# chalupa.net
KiCad netlist of a schematic drawn in EAGLE
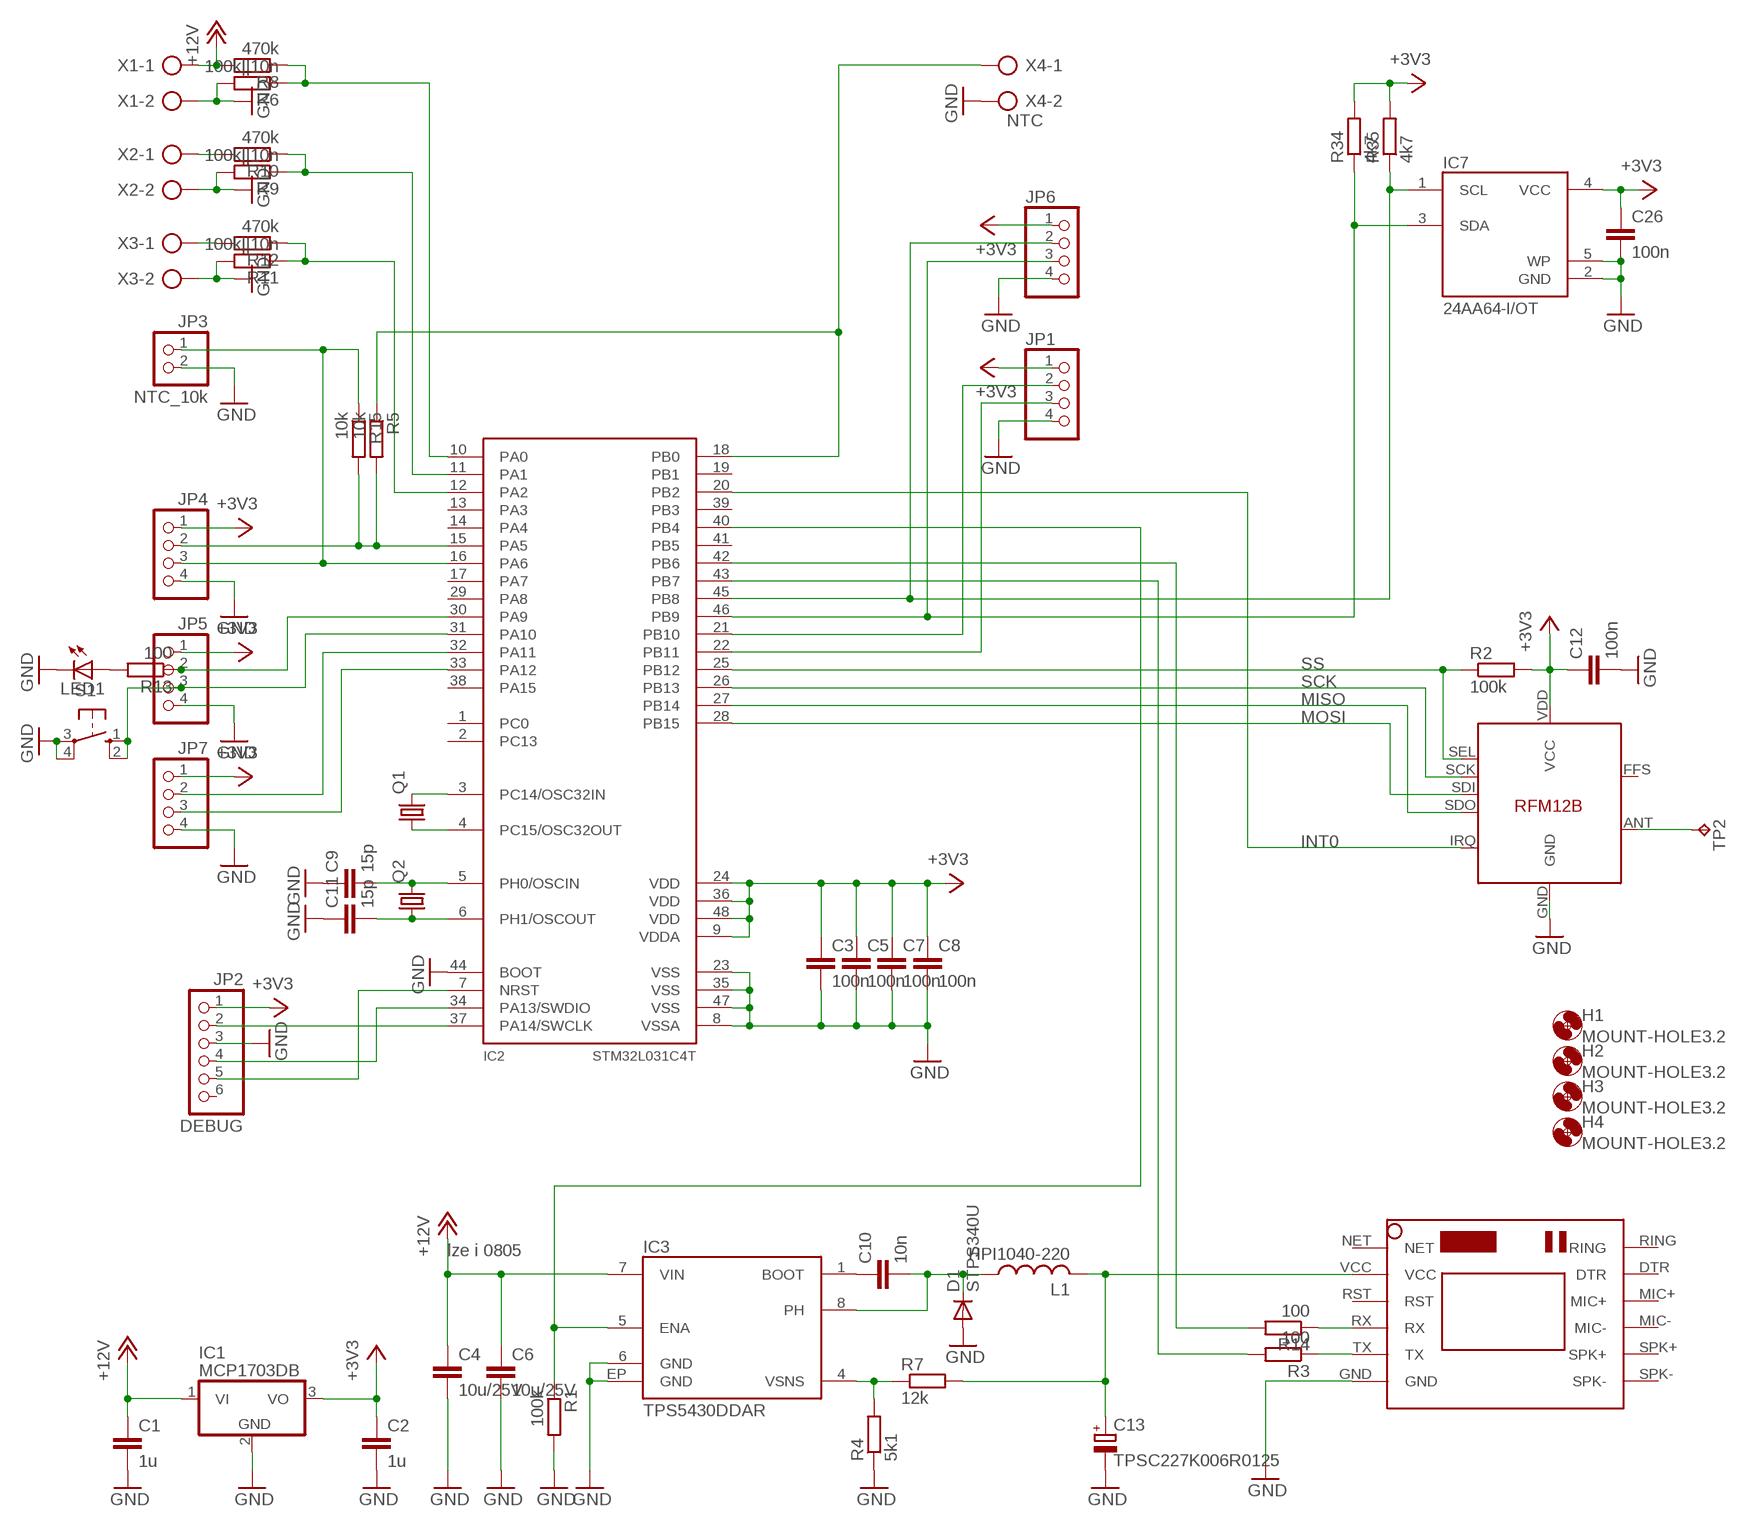
[diagram p0: schematic, sheet 1]

(export (version "E")
  (design (tool "Eeschema 10.0.6"))
  (components
    (comp (ref "C1")
      (value "1u")
      (footprint "eagle-import:C0603")
      (libsource (lib "eagle-import") (part "C-EUC0603"))
    )
    (comp (ref "C2")
      (value "1u")
      (footprint "eagle-import:C0603")
      (libsource (lib "eagle-import") (part "C-EUC0603"))
    )
    (comp (ref "C3")
      (value "100n")
      (footprint "eagle-import:C0603")
      (libsource (lib "eagle-import") (part "C-EUC0603"))
    )
    (comp (ref "C4")
      (value "10u/25V")
      (footprint "eagle-import:C1206")
      (libsource (lib "eagle-import") (part "C-EUC1206"))
    )
    (comp (ref "C5")
      (value "100n")
      (footprint "eagle-import:C0603")
      (libsource (lib "eagle-import") (part "C-EUC0603"))
    )
    (comp (ref "C6")
      (value "10u/25V")
      (footprint "eagle-import:C1206")
      (libsource (lib "eagle-import") (part "C-EUC1206"))
    )
    (comp (ref "C7")
      (value "100n")
      (footprint "eagle-import:C0603")
      (libsource (lib "eagle-import") (part "C-EUC0603"))
    )
    (comp (ref "C8")
      (value "100n")
      (footprint "eagle-import:C0603")
      (libsource (lib "eagle-import") (part "C-EUC0603"))
    )
    (comp (ref "C9")
      (value "15p")
      (footprint "eagle-import:C0603")
      (libsource (lib "eagle-import") (part "C-EUC0603"))
    )
    (comp (ref "C10")
      (value "10n")
      (footprint "eagle-import:C0603")
      (libsource (lib "eagle-import") (part "C-EUC0603"))
    )
    (comp (ref "C11")
      (value "15p")
      (footprint "eagle-import:C0603")
      (libsource (lib "eagle-import") (part "C-EUC0603"))
    )
    (comp (ref "C12")
      (value "100n")
      (footprint "eagle-import:C0603")
      (libsource (lib "eagle-import") (part "C-EUC0603"))
    )
    (comp (ref "C13")
      (value "TPSC227K006R0125")
      (footprint "eagle-import:SMC_C")
      (libsource (lib "eagle-import") (part "CPOL-EUSMCC"))
    )
    (comp (ref "C26")
      (value "100n")
      (footprint "eagle-import:C0603")
      (libsource (lib "eagle-import") (part "C-EUC0603"))
    )
    (comp (ref "D1")
      (value "STPS340U")
      (footprint "eagle-import:SMB")
      (libsource (lib "eagle-import") (part "DIODE-SMB"))
    )
    (comp (ref "H1")
      (value "MOUNT-HOLE3.2")
      (footprint "eagle-import:3,2")
      (libsource (lib "eagle-import") (part "MOUNT-HOLE3.2"))
    )
    (comp (ref "H2")
      (value "MOUNT-HOLE3.2")
      (footprint "eagle-import:3,2")
      (libsource (lib "eagle-import") (part "MOUNT-HOLE3.2"))
    )
    (comp (ref "H3")
      (value "MOUNT-HOLE3.2")
      (footprint "eagle-import:3,2")
      (libsource (lib "eagle-import") (part "MOUNT-HOLE3.2"))
    )
    (comp (ref "H4")
      (value "MOUNT-HOLE3.2")
      (footprint "eagle-import:3,2")
      (libsource (lib "eagle-import") (part "MOUNT-HOLE3.2"))
    )
    (comp (ref "IC1")
      (value "MCP1703DB")
      (footprint "eagle-import:SOT223")
      (libsource (lib "eagle-import") (part "MCP1703DB"))
    )
    (comp (ref "IC2")
      (value "STM32L031C4T")
      (footprint "eagle-import:LQFP48")
      (libsource (lib "eagle-import") (part "STM32L031C4T"))
    )
    (comp (ref "IC3")
      (value "TPS5430DDAR")
      (footprint "eagle-import:DDA")
      (libsource (lib "eagle-import") (part "TPS5430DDA"))
    )
    (comp (ref "IC5")
      (value "SIM800LMODULE")
      (footprint "eagle-import:SIM800LMODULE")
      (libsource (lib "eagle-import") (part "SIM800LMODULE"))
    )
    (comp (ref "IC7")
      (value "24AA64-I/OT")
      (footprint "eagle-import:SOT23-5")
      (libsource (lib "eagle-import") (part "24AA64-I/OT"))
    )
    (comp (ref "JP1")
      (value "PINHD-1X4")
      (footprint "eagle-import:1X04")
      (libsource (lib "eagle-import") (part "PINHD-1X4"))
    )
    (comp (ref "JP2")
      (value "DEBUG")
      (footprint "eagle-import:1X06")
      (libsource (lib "eagle-import") (part "PINHD-1X6"))
    )
    (comp (ref "JP3")
      (value "NTC_10k")
      (footprint "eagle-import:1X02")
      (libsource (lib "eagle-import") (part "PINHD-1X2"))
    )
    (comp (ref "JP4")
      (value "PINHD-1X4")
      (footprint "eagle-import:1X04")
      (libsource (lib "eagle-import") (part "PINHD-1X4"))
    )
    (comp (ref "JP5")
      (value "PINHD-1X4")
      (footprint "eagle-import:1X04")
      (libsource (lib "eagle-import") (part "PINHD-1X4"))
    )
    (comp (ref "JP6")
      (value "PINHD-1X4")
      (footprint "eagle-import:1X04")
      (libsource (lib "eagle-import") (part "PINHD-1X4"))
    )
    (comp (ref "JP7")
      (value "PINHD-1X4")
      (footprint "eagle-import:1X04")
      (libsource (lib "eagle-import") (part "PINHD-1X4"))
    )
    (comp (ref "L1")
      (value "HPI1040-220")
      (footprint "eagle-import:HPI1040")
      (libsource (lib "eagle-import") (part "L-USHPI1040"))
    )
    (comp (ref "LED1")
      (value "LEDCHIP-LED0805")
      (footprint "eagle-import:CHIP-LED0805")
      (libsource (lib "eagle-import") (part "LEDCHIP-LED0805"))
    )
    (comp (ref "Q1")
      (value "CRYSTALTC38H")
      (footprint "eagle-import:TC38H")
      (libsource (lib "eagle-import") (part "CRYSTALTC38H"))
    )
    (comp (ref "Q2")
      (value "CRYSTALHC49UP")
      (footprint "eagle-import:HC49UP")
      (libsource (lib "eagle-import") (part "CRYSTALHC49UP"))
    )
    (comp (ref "R1")
      (value "100k")
      (footprint "eagle-import:R0603")
      (libsource (lib "eagle-import") (part "R-EU_R0603"))
    )
    (comp (ref "R2")
      (value "100k")
      (footprint "eagle-import:R0603")
      (libsource (lib "eagle-import") (part "R-EU_R0603"))
    )
    (comp (ref "R3")
      (value "100")
      (footprint "eagle-import:R0603")
      (libsource (lib "eagle-import") (part "R-EU_R0603"))
    )
    (comp (ref "R4")
      (value "5k1")
      (footprint "eagle-import:R0603")
      (libsource (lib "eagle-import") (part "R-EU_R0603"))
    )
    (comp (ref "R5")
      (value "10k")
      (footprint "eagle-import:R0603")
      (libsource (lib "eagle-import") (part "R-EU_R0603"))
    )
    (comp (ref "R6")
      (value "100k||10n")
      (footprint "eagle-import:R0603")
      (libsource (lib "eagle-import") (part "R-EU_R0603"))
    )
    (comp (ref "R7")
      (value "12k")
      (footprint "eagle-import:R0603")
      (libsource (lib "eagle-import") (part "R-EU_R0603"))
    )
    (comp (ref "R8")
      (value "470k")
      (footprint "eagle-import:R0603")
      (libsource (lib "eagle-import") (part "R-EU_R0603"))
    )
    (comp (ref "R9")
      (value "100k||10n")
      (footprint "eagle-import:R0603")
      (libsource (lib "eagle-import") (part "R-EU_R0603"))
    )
    (comp (ref "R10")
      (value "470k")
      (footprint "eagle-import:R0603")
      (libsource (lib "eagle-import") (part "R-EU_R0603"))
    )
    (comp (ref "R11")
      (value "100k||10n")
      (footprint "eagle-import:R0603")
      (libsource (lib "eagle-import") (part "R-EU_R0603"))
    )
    (comp (ref "R12")
      (value "470k")
      (footprint "eagle-import:R0603")
      (libsource (lib "eagle-import") (part "R-EU_R0603"))
    )
    (comp (ref "R13")
      (value "100")
      (footprint "eagle-import:R0603")
      (libsource (lib "eagle-import") (part "R-EU_R0603"))
    )
    (comp (ref "R14")
      (value "100")
      (footprint "eagle-import:R0603")
      (libsource (lib "eagle-import") (part "R-EU_R0603"))
    )
    (comp (ref "R15")
      (value "10k")
      (footprint "eagle-import:R0603")
      (libsource (lib "eagle-import") (part "R-EU_R0603"))
    )
    (comp (ref "R34")
      (value "4k7")
      (footprint "eagle-import:R0603")
      (libsource (lib "eagle-import") (part "R-EU_R0603"))
    )
    (comp (ref "R35")
      (value "4k7")
      (footprint "eagle-import:R0603")
      (libsource (lib "eagle-import") (part "R-EU_R0603"))
    )
    (comp (ref "RFM12B")
      (value "RFM12B")
      (footprint "eagle-import:RFM12B")
      (libsource (lib "eagle-import") (part "RFM12B"))
    )
    (comp (ref "S1")
      (value "10-XX")
      (footprint "eagle-import:B3F-10XX")
      (fields (field (name "MPN") "B3F-1000"))
      (libsource (lib "eagle-import") (part "10-XX"))
    )
    (comp (ref "TP2")
      (value "TPB2,54")
      (footprint "eagle-import:B2,54")
      (libsource (lib "eagle-import") (part "TPB2,54"))
    )
    (comp (ref "X1")
      (value "AK500/2")
      (footprint "eagle-import:AK500_2")
      (libsource (lib "eagle-import") (part "AK500/2"))
    )
    (comp (ref "X2")
      (value "AK500/2")
      (footprint "eagle-import:AK500_2")
      (libsource (lib "eagle-import") (part "AK500/2"))
    )
    (comp (ref "X3")
      (value "AK500/2")
      (footprint "eagle-import:AK500_2")
      (libsource (lib "eagle-import") (part "AK500/2"))
    )
    (comp (ref "X4")
      (value "NTC")
      (footprint "eagle-import:AK500_2")
      (libsource (lib "eagle-import") (part "AK500/2"))
    )
  )
  (nets
    (net (code "1") (name "+3V3") (class "Default")
      (node (ref "C12") (pin "1") (pinfunction "1_1") (pintype "passive"))
      (node (ref "C2") (pin "1") (pinfunction "1_1") (pintype "passive"))
      (node (ref "C26") (pin "1") (pinfunction "1_1") (pintype "passive"))
      (node (ref "C3") (pin "1") (pinfunction "1_1") (pintype "passive"))
      (node (ref "C5") (pin "1") (pinfunction "1_1") (pintype "passive"))
      (node (ref "C7") (pin "1") (pinfunction "1_1") (pintype "passive"))
      (node (ref "C8") (pin "1") (pinfunction "1_1") (pintype "passive"))
      (node (ref "IC1") (pin "3") (pinfunction "VO_3") (pintype "passive"))
      (node (ref "IC2") (pin "24") (pinfunction "VDD_24") (pintype "power_in"))
      (node (ref "IC2") (pin "36") (pinfunction "VDD_36") (pintype "power_in"))
      (node (ref "IC2") (pin "48") (pinfunction "VDD_48") (pintype "power_in"))
      (node (ref "IC2") (pin "9") (pinfunction "VDDA_9") (pintype "power_in"))
      (node (ref "IC7") (pin "4") (pinfunction "VCC_4") (pintype "power_in"))
      (node (ref "JP1") (pin "1") (pinfunction "1_1") (pintype "passive"))
      (node (ref "JP2") (pin "1") (pinfunction "1_1") (pintype "passive"))
      (node (ref "JP4") (pin "1") (pinfunction "1_1") (pintype "passive"))
      (node (ref "JP5") (pin "1") (pinfunction "1_1") (pintype "passive"))
      (node (ref "JP6") (pin "1") (pinfunction "1_1") (pintype "passive"))
      (node (ref "JP7") (pin "1") (pinfunction "1_1") (pintype "passive"))
      (node (ref "R2") (pin "2") (pinfunction "2_2") (pintype "passive"))
      (node (ref "R34") (pin "2") (pinfunction "2_2") (pintype "passive"))
      (node (ref "R35") (pin "2") (pinfunction "2_2") (pintype "passive"))
      (node (ref "RFM12B") (pin "VDD") (pinfunction "VCC_VDD") (pintype "power_in"))
    )
    (net (code "2") (name "+12V") (class "Default")
      (node (ref "C1") (pin "1") (pinfunction "1_1") (pintype "passive"))
      (node (ref "C4") (pin "1") (pinfunction "1_1") (pintype "passive"))
      (node (ref "C6") (pin "1") (pinfunction "1_1") (pintype "passive"))
      (node (ref "IC1") (pin "1") (pinfunction "VI_1") (pintype "input"))
      (node (ref "IC3") (pin "7") (pinfunction "VIN_7") (pintype "power_in"))
      (node (ref "R8") (pin "2") (pinfunction "2_2") (pintype "passive"))
      (node (ref "X1") (pin "1") (pinfunction "KL_1") (pintype "passive"))
    )
    (net (code "3") (name "/INT0") (class "Default")
      (node (ref "IC2") (pin "20") (pinfunction "PB2_20") (pintype "bidirectional"))
      (node (ref "RFM12B") (pin "IRQ") (pinfunction "IRQ_IRQ") (pintype "open_collector"))
    )
    (net (code "4") (name "/MISO") (class "Default")
      (node (ref "IC2") (pin "27") (pinfunction "PB14_27") (pintype "bidirectional"))
      (node (ref "RFM12B") (pin "SDO") (pinfunction "SDO_SDO") (pintype "output"))
    )
    (net (code "5") (name "/MOSI") (class "Default")
      (node (ref "IC2") (pin "28") (pinfunction "PB15_28") (pintype "bidirectional"))
      (node (ref "RFM12B") (pin "SDI") (pinfunction "SDI_SDI") (pintype "input"))
    )
    (net (code "6") (name "/SCK") (class "Default")
      (node (ref "IC2") (pin "26") (pinfunction "PB13_26") (pintype "bidirectional"))
      (node (ref "RFM12B") (pin "SCK") (pinfunction "SCK_SCK") (pintype "input"))
    )
    (net (code "7") (name "/SS") (class "Default")
      (node (ref "IC2") (pin "25") (pinfunction "PB12_25") (pintype "bidirectional"))
      (node (ref "R2") (pin "1") (pinfunction "1_1") (pintype "passive"))
      (node (ref "RFM12B") (pin "SEL") (pinfunction "SEL_SEL") (pintype "input"))
    )
    (net (code "8") (name "GND") (class "Default")
      (node (ref "C1") (pin "2") (pinfunction "2_2") (pintype "passive"))
      (node (ref "C11") (pin "1") (pinfunction "1_1") (pintype "passive"))
      (node (ref "C12") (pin "2") (pinfunction "2_2") (pintype "passive"))
      (node (ref "C13") (pin "-") (pinfunction "-_-") (pintype "passive"))
      (node (ref "C2") (pin "2") (pinfunction "2_2") (pintype "passive"))
      (node (ref "C26") (pin "2") (pinfunction "2_2") (pintype "passive"))
      (node (ref "C3") (pin "2") (pinfunction "2_2") (pintype "passive"))
      (node (ref "C4") (pin "2") (pinfunction "2_2") (pintype "passive"))
      (node (ref "C5") (pin "2") (pinfunction "2_2") (pintype "passive"))
      (node (ref "C6") (pin "2") (pinfunction "2_2") (pintype "passive"))
      (node (ref "C7") (pin "2") (pinfunction "2_2") (pintype "passive"))
      (node (ref "C8") (pin "2") (pinfunction "2_2") (pintype "passive"))
      (node (ref "C9") (pin "1") (pinfunction "1_1") (pintype "passive"))
      (node (ref "D1") (pin "A") (pinfunction "A_A") (pintype "passive"))
      (node (ref "IC1") (pin "2") (pinfunction "GND_2") (pintype "passive"))
      (node (ref "IC2") (pin "23") (pinfunction "VSS_23") (pintype "power_in"))
      (node (ref "IC2") (pin "35") (pinfunction "VSS_35") (pintype "power_in"))
      (node (ref "IC2") (pin "44") (pinfunction "BOOT_44") (pintype "bidirectional"))
      (node (ref "IC2") (pin "47") (pinfunction "VSS_47") (pintype "power_in"))
      (node (ref "IC2") (pin "8") (pinfunction "VSSA_8") (pintype "power_in"))
      (node (ref "IC3") (pin "6") (pinfunction "GND_6") (pintype "power_in"))
      (node (ref "IC3") (pin "EP") (pinfunction "GND_EP") (pintype "power_in"))
      (node (ref "IC5") (pin "GND") (pinfunction "GND_GND") (pintype "bidirectional"))
      (node (ref "IC7") (pin "2") (pinfunction "GND_2") (pintype "power_in"))
      (node (ref "IC7") (pin "5") (pinfunction "WP_5") (pintype "input"))
      (node (ref "JP1") (pin "4") (pinfunction "4_4") (pintype "passive"))
      (node (ref "JP2") (pin "3") (pinfunction "3_3") (pintype "passive"))
      (node (ref "JP3") (pin "2") (pinfunction "2_2") (pintype "passive"))
      (node (ref "JP4") (pin "4") (pinfunction "4_4") (pintype "passive"))
      (node (ref "JP5") (pin "4") (pinfunction "4_4") (pintype "passive"))
      (node (ref "JP6") (pin "4") (pinfunction "4_4") (pintype "passive"))
      (node (ref "JP7") (pin "4") (pinfunction "4_4") (pintype "passive"))
      (node (ref "LED1") (pin "C") (pinfunction "C_C") (pintype "passive"))
      (node (ref "R1") (pin "2") (pinfunction "2_2") (pintype "passive"))
      (node (ref "R11") (pin "2") (pinfunction "2_2") (pintype "passive"))
      (node (ref "R4") (pin "1") (pinfunction "1_1") (pintype "passive"))
      (node (ref "R6") (pin "2") (pinfunction "2_2") (pintype "passive"))
      (node (ref "R9") (pin "2") (pinfunction "2_2") (pintype "passive"))
      (node (ref "RFM12B") (pin "GND") (pinfunction "GND_GND") (pintype "power_in"))
      (node (ref "S1") (pin "3") (pinfunction "P_3") (pintype "passive"))
      (node (ref "S1") (pin "4") (pinfunction "P1_4") (pintype "passive"))
      (node (ref "X1") (pin "2") (pinfunction "KL_2") (pintype "passive"))
      (node (ref "X2") (pin "2") (pinfunction "KL_2") (pintype "passive"))
      (node (ref "X3") (pin "2") (pinfunction "KL_2") (pintype "passive"))
      (node (ref "X4") (pin "2") (pinfunction "KL_2") (pintype "passive"))
    )
    (net (code "9") (name "Net-(C13-Pad+)") (class "Default")
      (node (ref "C13") (pin "+") (pinfunction "+_+") (pintype "passive"))
      (node (ref "IC5") (pin "VCC") (pinfunction "VCC_VCC") (pintype "bidirectional"))
      (node (ref "L1") (pin "2") (pinfunction "2_2") (pintype "passive"))
      (node (ref "R7") (pin "2") (pinfunction "2_2") (pintype "passive"))
    )
    (net (code "10") (name "Net-(IC2-NRST)") (class "Default")
      (node (ref "IC2") (pin "7") (pinfunction "NRST_7") (pintype "bidirectional"))
      (node (ref "JP2") (pin "5") (pinfunction "5_5") (pintype "passive"))
    )
    (net (code "11") (name "Net-(IC2-PA0)") (class "Default")
      (node (ref "IC2") (pin "10") (pinfunction "PA0_10") (pintype "bidirectional"))
      (node (ref "R6") (pin "1") (pinfunction "1_1") (pintype "passive"))
      (node (ref "R8") (pin "1") (pinfunction "1_1") (pintype "passive"))
    )
    (net (code "12") (name "Net-(IC2-PA1)") (class "Default")
      (node (ref "IC2") (pin "11") (pinfunction "PA1_11") (pintype "bidirectional"))
      (node (ref "R10") (pin "1") (pinfunction "1_1") (pintype "passive"))
      (node (ref "R9") (pin "1") (pinfunction "1_1") (pintype "passive"))
    )
    (net (code "13") (name "Net-(IC2-PA2)") (class "Default")
      (node (ref "IC2") (pin "12") (pinfunction "PA2_12") (pintype "bidirectional"))
      (node (ref "R11") (pin "1") (pinfunction "1_1") (pintype "passive"))
      (node (ref "R12") (pin "1") (pinfunction "1_1") (pintype "passive"))
    )
    (net (code "14") (name "Net-(IC2-PA5)") (class "Default")
      (node (ref "IC2") (pin "15") (pinfunction "PA5_15") (pintype "bidirectional"))
      (node (ref "JP4") (pin "2") (pinfunction "2_2") (pintype "passive"))
      (node (ref "R15") (pin "2") (pinfunction "2_2") (pintype "passive"))
      (node (ref "R5") (pin "2") (pinfunction "2_2") (pintype "passive"))
    )
    (net (code "15") (name "Net-(IC2-PA6)") (class "Default")
      (node (ref "IC2") (pin "16") (pinfunction "PA6_16") (pintype "bidirectional"))
      (node (ref "JP3") (pin "1") (pinfunction "1_1") (pintype "passive"))
      (node (ref "JP4") (pin "3") (pinfunction "3_3") (pintype "passive"))
      (node (ref "R15") (pin "1") (pinfunction "1_1") (pintype "passive"))
    )
    (net (code "16") (name "Net-(IC2-PA9)") (class "Default")
      (node (ref "IC2") (pin "30") (pinfunction "PA9_30") (pintype "bidirectional"))
      (node (ref "JP5") (pin "2") (pinfunction "2_2") (pintype "passive"))
      (node (ref "R13") (pin "1") (pinfunction "1_1") (pintype "passive"))
    )
    (net (code "17") (name "Net-(IC2-PA10)") (class "Default")
      (node (ref "IC2") (pin "31") (pinfunction "PA10_31") (pintype "bidirectional"))
      (node (ref "JP5") (pin "3") (pinfunction "3_3") (pintype "passive"))
      (node (ref "S1") (pin "1") (pinfunction "S_1") (pintype "passive"))
      (node (ref "S1") (pin "2") (pinfunction "S1_2") (pintype "passive"))
    )
    (net (code "18") (name "Net-(IC2-PA11)") (class "Default")
      (node (ref "IC2") (pin "32") (pinfunction "PA11_32") (pintype "bidirectional"))
      (node (ref "JP7") (pin "2") (pinfunction "2_2") (pintype "passive"))
    )
    (net (code "19") (name "Net-(IC2-PA12)") (class "Default")
      (node (ref "IC2") (pin "33") (pinfunction "PA12_33") (pintype "bidirectional"))
      (node (ref "JP7") (pin "3") (pinfunction "3_3") (pintype "passive"))
    )
    (net (code "20") (name "Net-(IC2-PA13{slash}SWDIO)") (class "Default")
      (node (ref "IC2") (pin "34") (pinfunction "PA13/SWDIO_34") (pintype "bidirectional"))
      (node (ref "JP2") (pin "4") (pinfunction "4_4") (pintype "passive"))
    )
    (net (code "21") (name "Net-(IC2-PA14{slash}SWCLK)") (class "Default")
      (node (ref "IC2") (pin "37") (pinfunction "PA14/SWCLK_37") (pintype "bidirectional"))
      (node (ref "JP2") (pin "2") (pinfunction "2_2") (pintype "passive"))
    )
    (net (code "22") (name "Net-(IC2-PB0)") (class "Default")
      (node (ref "IC2") (pin "18") (pinfunction "PB0_18") (pintype "bidirectional"))
      (node (ref "R5") (pin "1") (pinfunction "1_1") (pintype "passive"))
      (node (ref "X4") (pin "1") (pinfunction "KL_1") (pintype "passive"))
    )
    (net (code "23") (name "Net-(IC2-PB4)") (class "Default")
      (node (ref "IC2") (pin "40") (pinfunction "PB4_40") (pintype "bidirectional"))
      (node (ref "IC3") (pin "5") (pinfunction "ENA_5") (pintype "bidirectional"))
      (node (ref "R1") (pin "1") (pinfunction "1_1") (pintype "passive"))
    )
    (net (code "24") (name "Net-(IC2-PB6)") (class "Default")
      (node (ref "IC2") (pin "42") (pinfunction "PB6_42") (pintype "bidirectional"))
      (node (ref "R14") (pin "2") (pinfunction "2_2") (pintype "passive"))
    )
    (net (code "25") (name "Net-(IC2-PB7)") (class "Default")
      (node (ref "IC2") (pin "43") (pinfunction "PB7_43") (pintype "bidirectional"))
      (node (ref "R3") (pin "2") (pinfunction "2_2") (pintype "passive"))
    )
    (net (code "26") (name "Net-(IC2-PB8)") (class "Default")
      (node (ref "IC2") (pin "45") (pinfunction "PB8_45") (pintype "bidirectional"))
      (node (ref "IC7") (pin "1") (pinfunction "SCL_1") (pintype "input"))
      (node (ref "JP6") (pin "2") (pinfunction "2_2") (pintype "passive"))
      (node (ref "R35") (pin "1") (pinfunction "1_1") (pintype "passive"))
    )
    (net (code "27") (name "Net-(IC2-PB9)") (class "Default")
      (node (ref "IC2") (pin "46") (pinfunction "PB9_46") (pintype "bidirectional"))
      (node (ref "IC7") (pin "3") (pinfunction "SDA_3") (pintype "bidirectional"))
      (node (ref "JP6") (pin "3") (pinfunction "3_3") (pintype "passive"))
      (node (ref "R34") (pin "1") (pinfunction "1_1") (pintype "passive"))
    )
    (net (code "28") (name "Net-(IC2-PB10)") (class "Default")
      (node (ref "IC2") (pin "21") (pinfunction "PB10_21") (pintype "bidirectional"))
      (node (ref "JP1") (pin "2") (pinfunction "2_2") (pintype "passive"))
    )
    (net (code "29") (name "Net-(IC2-PB11)") (class "Default")
      (node (ref "IC2") (pin "22") (pinfunction "PB11_22") (pintype "bidirectional"))
      (node (ref "JP1") (pin "3") (pinfunction "3_3") (pintype "passive"))
    )
    (net (code "30") (name "Net-(IC2-PC14{slash}OSC32IN)") (class "Default")
      (node (ref "IC2") (pin "3") (pinfunction "PC14/OSC32IN_3") (pintype "passive"))
      (node (ref "Q1") (pin "2") (pinfunction "2_2") (pintype "passive"))
    )
    (net (code "31") (name "Net-(IC2-PC15{slash}OSC32OUT)") (class "Default")
      (node (ref "IC2") (pin "4") (pinfunction "PC15/OSC32OUT_4") (pintype "passive"))
      (node (ref "Q1") (pin "1") (pinfunction "1_1") (pintype "passive"))
    )
    (net (code "32") (name "Net-(IC2-PH0{slash}OSCIN)") (class "Default")
      (node (ref "C9") (pin "2") (pinfunction "2_2") (pintype "passive"))
      (node (ref "IC2") (pin "5") (pinfunction "PH0/OSCIN_5") (pintype "passive"))
      (node (ref "Q2") (pin "2") (pinfunction "2_2") (pintype "passive"))
    )
    (net (code "33") (name "Net-(IC2-PH1{slash}OSCOUT)") (class "Default")
      (node (ref "C11") (pin "2") (pinfunction "2_2") (pintype "passive"))
      (node (ref "IC2") (pin "6") (pinfunction "PH1/OSCOUT_6") (pintype "passive"))
      (node (ref "Q2") (pin "1") (pinfunction "1_1") (pintype "passive"))
    )
    (net (code "34") (name "Net-(IC3-BOOT)") (class "Default")
      (node (ref "C10") (pin "1") (pinfunction "1_1") (pintype "passive"))
      (node (ref "IC3") (pin "1") (pinfunction "BOOT_1") (pintype "passive"))
    )
    (net (code "35") (name "Net-(IC3-PH)") (class "Default")
      (node (ref "C10") (pin "2") (pinfunction "2_2") (pintype "passive"))
      (node (ref "D1") (pin "C") (pinfunction "C_C") (pintype "passive"))
      (node (ref "IC3") (pin "8") (pinfunction "PH_8") (pintype "passive"))
      (node (ref "L1") (pin "1") (pinfunction "1_1") (pintype "passive"))
    )
    (net (code "36") (name "Net-(IC3-VSNS)") (class "Default")
      (node (ref "IC3") (pin "4") (pinfunction "VSNS_4") (pintype "input"))
      (node (ref "R4") (pin "2") (pinfunction "2_2") (pintype "passive"))
      (node (ref "R7") (pin "1") (pinfunction "1_1") (pintype "passive"))
    )
    (net (code "37") (name "Net-(IC5-PadRX)") (class "Default")
      (node (ref "IC5") (pin "RX") (pinfunction "RX_RX") (pintype "bidirectional"))
      (node (ref "R14") (pin "1") (pinfunction "1_1") (pintype "passive"))
    )
    (net (code "38") (name "Net-(IC5-PadTX)") (class "Default")
      (node (ref "IC5") (pin "TX") (pinfunction "TX_TX") (pintype "bidirectional"))
      (node (ref "R3") (pin "1") (pinfunction "1_1") (pintype "passive"))
    )
    (net (code "39") (name "Net-(LED1-PadA)") (class "Default")
      (node (ref "LED1") (pin "A") (pinfunction "A_A") (pintype "passive"))
      (node (ref "R13") (pin "2") (pinfunction "2_2") (pintype "passive"))
    )
    (net (code "40") (name "Net-(TP2-TP)") (class "Default")
      (node (ref "RFM12B") (pin "ANT") (pinfunction "ANT_ANT") (pintype "passive"))
      (node (ref "TP2") (pin "PP") (pinfunction "TP_PP") (pintype "input"))
    )
    (net (code "41") (name "Net-(X2A-KL)") (class "Default")
      (node (ref "R10") (pin "2") (pinfunction "2_2") (pintype "passive"))
      (node (ref "X2") (pin "1") (pinfunction "KL_1") (pintype "passive"))
    )
    (net (code "42") (name "Net-(X3A-KL)") (class "Default")
      (node (ref "R12") (pin "2") (pinfunction "2_2") (pintype "passive"))
      (node (ref "X3") (pin "1") (pinfunction "KL_1") (pintype "passive"))
    )
    (net (code "43") (name "unconnected-(IC2-PA3-Pad13)") (class "Default")
      (node (ref "IC2") (pin "13") (pinfunction "PA3_13") (pintype "bidirectional"))
    )
    (net (code "44") (name "unconnected-(IC2-PA4-Pad14)") (class "Default")
      (node (ref "IC2") (pin "14") (pinfunction "PA4_14") (pintype "bidirectional"))
    )
    (net (code "45") (name "unconnected-(IC2-PA7-Pad17)") (class "Default")
      (node (ref "IC2") (pin "17") (pinfunction "PA7_17") (pintype "bidirectional"))
    )
    (net (code "46") (name "unconnected-(IC2-PA8-Pad29)") (class "Default")
      (node (ref "IC2") (pin "29") (pinfunction "PA8_29") (pintype "bidirectional"))
    )
    (net (code "47") (name "unconnected-(IC2-PA15-Pad38)") (class "Default")
      (node (ref "IC2") (pin "38") (pinfunction "PA15_38") (pintype "bidirectional"))
    )
    (net (code "48") (name "unconnected-(IC2-PB1-Pad19)") (class "Default")
      (node (ref "IC2") (pin "19") (pinfunction "PB1_19") (pintype "bidirectional"))
    )
    (net (code "49") (name "unconnected-(IC2-PB3-Pad39)") (class "Default")
      (node (ref "IC2") (pin "39") (pinfunction "PB3_39") (pintype "bidirectional"))
    )
    (net (code "50") (name "unconnected-(IC2-PB5-Pad41)") (class "Default")
      (node (ref "IC2") (pin "41") (pinfunction "PB5_41") (pintype "bidirectional"))
    )
    (net (code "51") (name "unconnected-(IC2-PC0-Pad1)") (class "Default")
      (node (ref "IC2") (pin "1") (pinfunction "PC0_1") (pintype "bidirectional"))
    )
    (net (code "52") (name "unconnected-(IC2-PC13-Pad2)") (class "Default")
      (node (ref "IC2") (pin "2") (pinfunction "PC13_2") (pintype "bidirectional"))
    )
    (net (code "53") (name "unconnected-(IC5-PadDTR)") (class "Default")
      (node (ref "IC5") (pin "DTR") (pinfunction "DTR_DTR") (pintype "bidirectional"))
    )
    (net (code "54") (name "unconnected-(IC5-PadMIC+)") (class "Default")
      (node (ref "IC5") (pin "MIC+") (pinfunction "MIC+_MIC+") (pintype "bidirectional"))
    )
    (net (code "55") (name "unconnected-(IC5-PadMIC-)") (class "Default")
      (node (ref "IC5") (pin "MIC-") (pinfunction "MIC-_MIC-") (pintype "bidirectional"))
    )
    (net (code "56") (name "unconnected-(IC5-PadNET)") (class "Default")
      (node (ref "IC5") (pin "NET") (pinfunction "NET_NET") (pintype "bidirectional"))
    )
    (net (code "57") (name "unconnected-(IC5-PadRING)") (class "Default")
      (node (ref "IC5") (pin "RING") (pinfunction "RING_RING") (pintype "bidirectional"))
    )
    (net (code "58") (name "unconnected-(IC5-PadRST)") (class "Default")
      (node (ref "IC5") (pin "RST") (pinfunction "RST_RST") (pintype "bidirectional"))
    )
    (net (code "59") (name "unconnected-(IC5-PadSPK+)") (class "Default")
      (node (ref "IC5") (pin "SPK+") (pinfunction "SPK+_SPK+") (pintype "bidirectional"))
    )
    (net (code "60") (name "unconnected-(IC5-PadSPK-)") (class "Default")
      (node (ref "IC5") (pin "SPK-") (pinfunction "SPK-_SPK-") (pintype "bidirectional"))
    )
    (net (code "61") (name "unconnected-(JP2-Pad6)") (class "Default")
      (node (ref "JP2") (pin "6") (pinfunction "6_6") (pintype "passive"))
    )
    (net (code "62") (name "unconnected-(RFM12B-PadFFS)") (class "Default")
      (node (ref "RFM12B") (pin "FFS") (pinfunction "FFS_FFS") (pintype "bidirectional"))
    )
  )
)
